# General_Tranceivers.net
KiCad netlist of a schematic drawn in Altium Designer
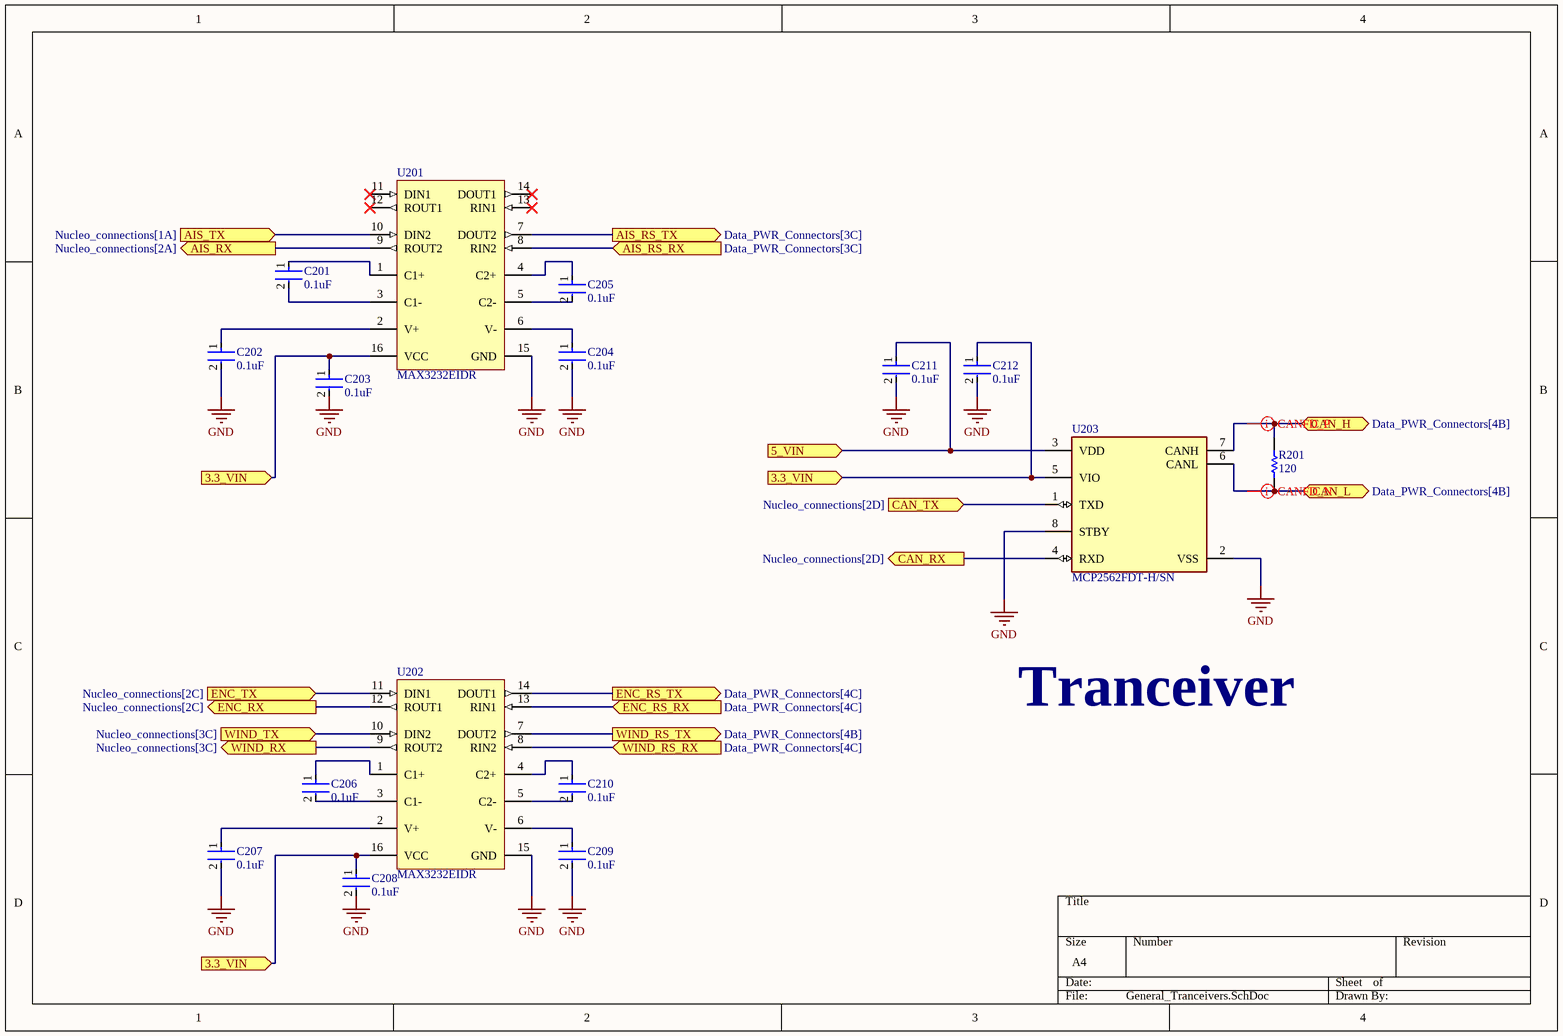
[diagram p0: General_Tranceivers.SchDoc]

(export (version "E")
  (design (tool "Eeschema 10.0.6"))
  (components
    (comp (ref "C201")
      (value "0.1uF")
      (footprint "FP-GCM21B-0_15-MFG")
      (description "Ceramic Capacitor for Automotive 100nF ±10% 100VDC X7R 0805 Embossed T/R")
      (fields (field (name "TOLERANCE") "10%") (field (name "VOLTAGE") "100V"))
      (libsource (lib "Altium Content Vault") (part "02cd4be3c70576c341d710602a673aa"))
    )
    (comp (ref "C202")
      (value "0.1uF")
      (footprint "FP-GCM21B-0_15-MFG")
      (description "Ceramic Capacitor for Automotive 100nF ±10% 100VDC X7R 0805 Embossed T/R")
      (fields (field (name "TOLERANCE") "10%") (field (name "VOLTAGE") "100V"))
      (libsource (lib "Altium Content Vault") (part "02cd4be3c70576c341d710602a673aa"))
    )
    (comp (ref "C203")
      (value "0.1uF")
      (footprint "FP-GCM21B-0_15-MFG")
      (description "Ceramic Capacitor for Automotive 100nF ±10% 100VDC X7R 0805 Embossed T/R")
      (fields (field (name "TOLERANCE") "10%") (field (name "VOLTAGE") "100V"))
      (libsource (lib "Altium Content Vault") (part "02cd4be3c70576c341d710602a673aa"))
    )
    (comp (ref "C204")
      (value "0.1uF")
      (footprint "FP-GCM21B-0_15-MFG")
      (description "Ceramic Capacitor for Automotive 100nF ±10% 100VDC X7R 0805 Embossed T/R")
      (fields (field (name "TOLERANCE") "10%") (field (name "VOLTAGE") "100V"))
      (libsource (lib "Altium Content Vault") (part "02cd4be3c70576c341d710602a673aa"))
    )
    (comp (ref "C205")
      (value "0.1uF")
      (footprint "FP-GCM21B-0_15-MFG")
      (description "Ceramic Capacitor for Automotive 100nF ±10% 100VDC X7R 0805 Embossed T/R")
      (fields (field (name "TOLERANCE") "10%") (field (name "VOLTAGE") "100V"))
      (libsource (lib "Altium Content Vault") (part "02cd4be3c70576c341d710602a673aa"))
    )
    (comp (ref "C206")
      (value "0.1uF")
      (footprint "FP-GCM21B-0_15-MFG")
      (description "Ceramic Capacitor for Automotive 100nF ±10% 100VDC X7R 0805 Embossed T/R")
      (fields (field (name "TOLERANCE") "10%") (field (name "VOLTAGE") "100V"))
      (libsource (lib "Altium Content Vault") (part "02cd4be3c70576c341d710602a673aa"))
    )
    (comp (ref "C207")
      (value "0.1uF")
      (footprint "FP-GCM21B-0_15-MFG")
      (description "Ceramic Capacitor for Automotive 100nF ±10% 100VDC X7R 0805 Embossed T/R")
      (fields (field (name "TOLERANCE") "10%") (field (name "VOLTAGE") "100V"))
      (libsource (lib "Altium Content Vault") (part "02cd4be3c70576c341d710602a673aa"))
    )
    (comp (ref "C208")
      (value "0.1uF")
      (footprint "FP-GCM21B-0_15-MFG")
      (description "Ceramic Capacitor for Automotive 100nF ±10% 100VDC X7R 0805 Embossed T/R")
      (fields (field (name "TOLERANCE") "10%") (field (name "VOLTAGE") "100V"))
      (libsource (lib "Altium Content Vault") (part "02cd4be3c70576c341d710602a673aa"))
    )
    (comp (ref "C209")
      (value "0.1uF")
      (footprint "FP-GCM21B-0_15-MFG")
      (description "Ceramic Capacitor for Automotive 100nF ±10% 100VDC X7R 0805 Embossed T/R")
      (fields (field (name "TOLERANCE") "10%") (field (name "VOLTAGE") "100V"))
      (libsource (lib "Altium Content Vault") (part "02cd4be3c70576c341d710602a673aa"))
    )
    (comp (ref "C210")
      (value "0.1uF")
      (footprint "FP-GCM21B-0_15-MFG")
      (description "Ceramic Capacitor for Automotive 100nF ±10% 100VDC X7R 0805 Embossed T/R")
      (fields (field (name "TOLERANCE") "10%") (field (name "VOLTAGE") "100V"))
      (libsource (lib "Altium Content Vault") (part "02cd4be3c70576c341d710602a673aa"))
    )
    (comp (ref "C211")
      (value "0.1uF")
      (footprint "FP-GCM21B-0_15-MFG")
      (description "Ceramic Capacitor for Automotive 100nF ±10% 100VDC X7R 0805 Embossed T/R")
      (fields (field (name "TOLERANCE") "10%") (field (name "VOLTAGE") "100V"))
      (libsource (lib "Altium Content Vault") (part "02cd4be3c70576c341d710602a673aa"))
    )
    (comp (ref "C212")
      (value "0.1uF")
      (footprint "FP-GCM21B-0_15-MFG")
      (description "Ceramic Capacitor for Automotive 100nF ±10% 100VDC X7R 0805 Embossed T/R")
      (fields (field (name "TOLERANCE") "10%") (field (name "VOLTAGE") "100V"))
      (libsource (lib "Altium Content Vault") (part "02cd4be3c70576c341d710602a673aa"))
    )
    (comp (ref "R201")
      (value "120")
      (footprint "RESC2013X60X35ML10T20")
      (description "Chip Resistor, 1 KOhm, +/- 1%, 125 mW, -55 to 155 degC, 0805 (2012 Metric), RoHS, Tape and Reel")
      (fields (field (name "TOLERANCE") "1%") (field (name "MANUFACTURER") "Yageo"))
      (libsource (lib "Altium Content Vault") (part "RES-2"))
    )
    (comp (ref "U201")
      (value "MAX3232EIDR")
      (footprint "D0016A_N")
      (libsource (lib "Altium Content Vault") (part "TI-MAX3232E-SOIC_D-16"))
    )
    (comp (ref "U202")
      (value "MAX3232EIDR")
      (footprint "D0016A_N")
      (libsource (lib "Altium Content Vault") (part "TI-MAX3232E-SOIC_D-16"))
    )
    (comp (ref "U203")
      (value "MCP2562FDT-H/SN")
      (footprint "FP-C04-057-SN-IPC_A")
      (description "IC TRANSCEIVER 1/1 8SOIC")
      (libsource (lib "Altium Content Vault") (part "d4eccbb03d796c5d2cef85367bb866b"))
    )
  )
  (nets
    (net (code "1") (name "/3.3_VIN") (class "Default")
      (node (ref "C203") (pin "1") (pinfunction "1_1") (pintype "passive"))
      (node (ref "C208") (pin "1") (pinfunction "1_1") (pintype "passive"))
      (node (ref "C212") (pin "1") (pinfunction "1_1") (pintype "passive"))
      (node (ref "U201") (pin "16") (pinfunction "VCC_16") (pintype "power_in"))
      (node (ref "U202") (pin "16") (pinfunction "VCC_16") (pintype "power_in"))
      (node (ref "U203") (pin "5") (pinfunction "VIO_5") (pintype "power_in"))
    )
    (net (code "2") (name "/5_VIN") (class "Default")
      (node (ref "C211") (pin "1") (pinfunction "1_1") (pintype "passive"))
      (node (ref "U203") (pin "3") (pinfunction "VDD_3") (pintype "power_in"))
    )
    (net (code "3") (name "/AIS_RS_RX") (class "Default")
      (node (ref "U201") (pin "8") (pinfunction "RIN2_8") (pintype "input"))
    )
    (net (code "4") (name "/AIS_RS_TX") (class "Default")
      (node (ref "U201") (pin "7") (pinfunction "DOUT2_7") (pintype "output"))
    )
    (net (code "5") (name "/AIS_RX") (class "Default")
      (node (ref "U201") (pin "9") (pinfunction "ROUT2_9") (pintype "output"))
    )
    (net (code "6") (name "/AIS_TX") (class "Default")
      (node (ref "U201") (pin "10") (pinfunction "DIN2_10") (pintype "input"))
    )
    (net (code "7") (name "/CAN_H") (class "Default")
      (node (ref "R201") (pin "1") (pinfunction "1_1") (pintype "passive"))
      (node (ref "U203") (pin "7") (pinfunction "CANH_7") (pintype "passive"))
    )
    (net (code "8") (name "/CAN_L") (class "Default")
      (node (ref "R201") (pin "2") (pinfunction "2_2") (pintype "passive"))
      (node (ref "U203") (pin "6") (pinfunction "CANL_6") (pintype "passive"))
    )
    (net (code "9") (name "/CAN_RX") (class "Default")
      (node (ref "U203") (pin "4") (pinfunction "RXD_4") (pintype "bidirectional"))
    )
    (net (code "10") (name "/CAN_TX") (class "Default")
      (node (ref "U203") (pin "1") (pinfunction "TXD_1") (pintype "bidirectional"))
    )
    (net (code "11") (name "/ENC_RS_RX") (class "Default")
      (node (ref "U202") (pin "13") (pinfunction "RIN1_13") (pintype "input"))
    )
    (net (code "12") (name "/ENC_RS_TX") (class "Default")
      (node (ref "U202") (pin "14") (pinfunction "DOUT1_14") (pintype "output"))
    )
    (net (code "13") (name "/ENC_RX") (class "Default")
      (node (ref "U202") (pin "12") (pinfunction "ROUT1_12") (pintype "output"))
    )
    (net (code "14") (name "/ENC_TX") (class "Default")
      (node (ref "U202") (pin "11") (pinfunction "DIN1_11") (pintype "input"))
    )
    (net (code "15") (name "/WIND_RS_RX") (class "Default")
      (node (ref "U202") (pin "8") (pinfunction "RIN2_8") (pintype "input"))
    )
    (net (code "16") (name "/WIND_RS_TX") (class "Default")
      (node (ref "U202") (pin "7") (pinfunction "DOUT2_7") (pintype "output"))
    )
    (net (code "17") (name "/WIND_RX") (class "Default")
      (node (ref "U202") (pin "9") (pinfunction "ROUT2_9") (pintype "output"))
    )
    (net (code "18") (name "/WIND_TX") (class "Default")
      (node (ref "U202") (pin "10") (pinfunction "DIN2_10") (pintype "input"))
    )
    (net (code "19") (name "GND") (class "Default")
      (node (ref "C202") (pin "2") (pinfunction "2_2") (pintype "passive"))
      (node (ref "C203") (pin "2") (pinfunction "2_2") (pintype "passive"))
      (node (ref "C204") (pin "2") (pinfunction "2_2") (pintype "passive"))
      (node (ref "C207") (pin "2") (pinfunction "2_2") (pintype "passive"))
      (node (ref "C208") (pin "2") (pinfunction "2_2") (pintype "passive"))
      (node (ref "C209") (pin "2") (pinfunction "2_2") (pintype "passive"))
      (node (ref "C211") (pin "2") (pinfunction "2_2") (pintype "passive"))
      (node (ref "C212") (pin "2") (pinfunction "2_2") (pintype "passive"))
      (node (ref "U201") (pin "15") (pinfunction "GND_15") (pintype "power_in"))
      (node (ref "U202") (pin "15") (pinfunction "GND_15") (pintype "power_in"))
      (node (ref "U203") (pin "2") (pinfunction "VSS_2") (pintype "power_in"))
      (node (ref "U203") (pin "8") (pinfunction "STBY_8") (pintype "passive"))
    )
    (net (code "20") (name "Net-(U201-C1+)") (class "Default")
      (node (ref "C201") (pin "1") (pinfunction "1_1") (pintype "passive"))
      (node (ref "U201") (pin "1") (pinfunction "C1+_1") (pintype "passive"))
    )
    (net (code "21") (name "Net-(U201-C1-)") (class "Default")
      (node (ref "C201") (pin "2") (pinfunction "2_2") (pintype "passive"))
      (node (ref "U201") (pin "3") (pinfunction "C1-_3") (pintype "passive"))
    )
    (net (code "22") (name "Net-(U201-C2+)") (class "Default")
      (node (ref "C205") (pin "1") (pinfunction "1_1") (pintype "passive"))
      (node (ref "U201") (pin "4") (pinfunction "C2+_4") (pintype "passive"))
    )
    (net (code "23") (name "Net-(U201-C2-)") (class "Default")
      (node (ref "C205") (pin "2") (pinfunction "2_2") (pintype "passive"))
      (node (ref "U201") (pin "5") (pinfunction "C2-_5") (pintype "passive"))
    )
    (net (code "24") (name "Net-(U201-V+)") (class "Default")
      (node (ref "C202") (pin "1") (pinfunction "1_1") (pintype "passive"))
      (node (ref "U201") (pin "2") (pinfunction "V+_2") (pintype "power_in"))
    )
    (net (code "25") (name "Net-(U201-V-)") (class "Default")
      (node (ref "C204") (pin "1") (pinfunction "1_1") (pintype "passive"))
      (node (ref "U201") (pin "6") (pinfunction "V-_6") (pintype "power_in"))
    )
    (net (code "26") (name "Net-(U202-C1+)") (class "Default")
      (node (ref "C206") (pin "1") (pinfunction "1_1") (pintype "passive"))
      (node (ref "U202") (pin "1") (pinfunction "C1+_1") (pintype "passive"))
    )
    (net (code "27") (name "Net-(U202-C1-)") (class "Default")
      (node (ref "C206") (pin "2") (pinfunction "2_2") (pintype "passive"))
      (node (ref "U202") (pin "3") (pinfunction "C1-_3") (pintype "passive"))
    )
    (net (code "28") (name "Net-(U202-C2+)") (class "Default")
      (node (ref "C210") (pin "1") (pinfunction "1_1") (pintype "passive"))
      (node (ref "U202") (pin "4") (pinfunction "C2+_4") (pintype "passive"))
    )
    (net (code "29") (name "Net-(U202-C2-)") (class "Default")
      (node (ref "C210") (pin "2") (pinfunction "2_2") (pintype "passive"))
      (node (ref "U202") (pin "5") (pinfunction "C2-_5") (pintype "passive"))
    )
    (net (code "30") (name "Net-(U202-V+)") (class "Default")
      (node (ref "C207") (pin "1") (pinfunction "1_1") (pintype "passive"))
      (node (ref "U202") (pin "2") (pinfunction "V+_2") (pintype "power_in"))
    )
    (net (code "31") (name "Net-(U202-V-)") (class "Default")
      (node (ref "C209") (pin "1") (pinfunction "1_1") (pintype "passive"))
      (node (ref "U202") (pin "6") (pinfunction "V-_6") (pintype "power_in"))
    )
    (net (code "32") (name "unconnected-(U201-DIN1-Pad11)") (class "Default")
      (node (ref "U201") (pin "11") (pinfunction "DIN1_11") (pintype "input+no_connect"))
    )
    (net (code "33") (name "unconnected-(U201-DOUT1-Pad14)") (class "Default")
      (node (ref "U201") (pin "14") (pinfunction "DOUT1_14") (pintype "output+no_connect"))
    )
    (net (code "34") (name "unconnected-(U201-RIN1-Pad13)") (class "Default")
      (node (ref "U201") (pin "13") (pinfunction "RIN1_13") (pintype "input+no_connect"))
    )
    (net (code "35") (name "unconnected-(U201-ROUT1-Pad12)") (class "Default")
      (node (ref "U201") (pin "12") (pinfunction "ROUT1_12") (pintype "output+no_connect"))
    )
  )
)
